# TE0722.net
KiCad netlist of a schematic drawn in Altium Designer
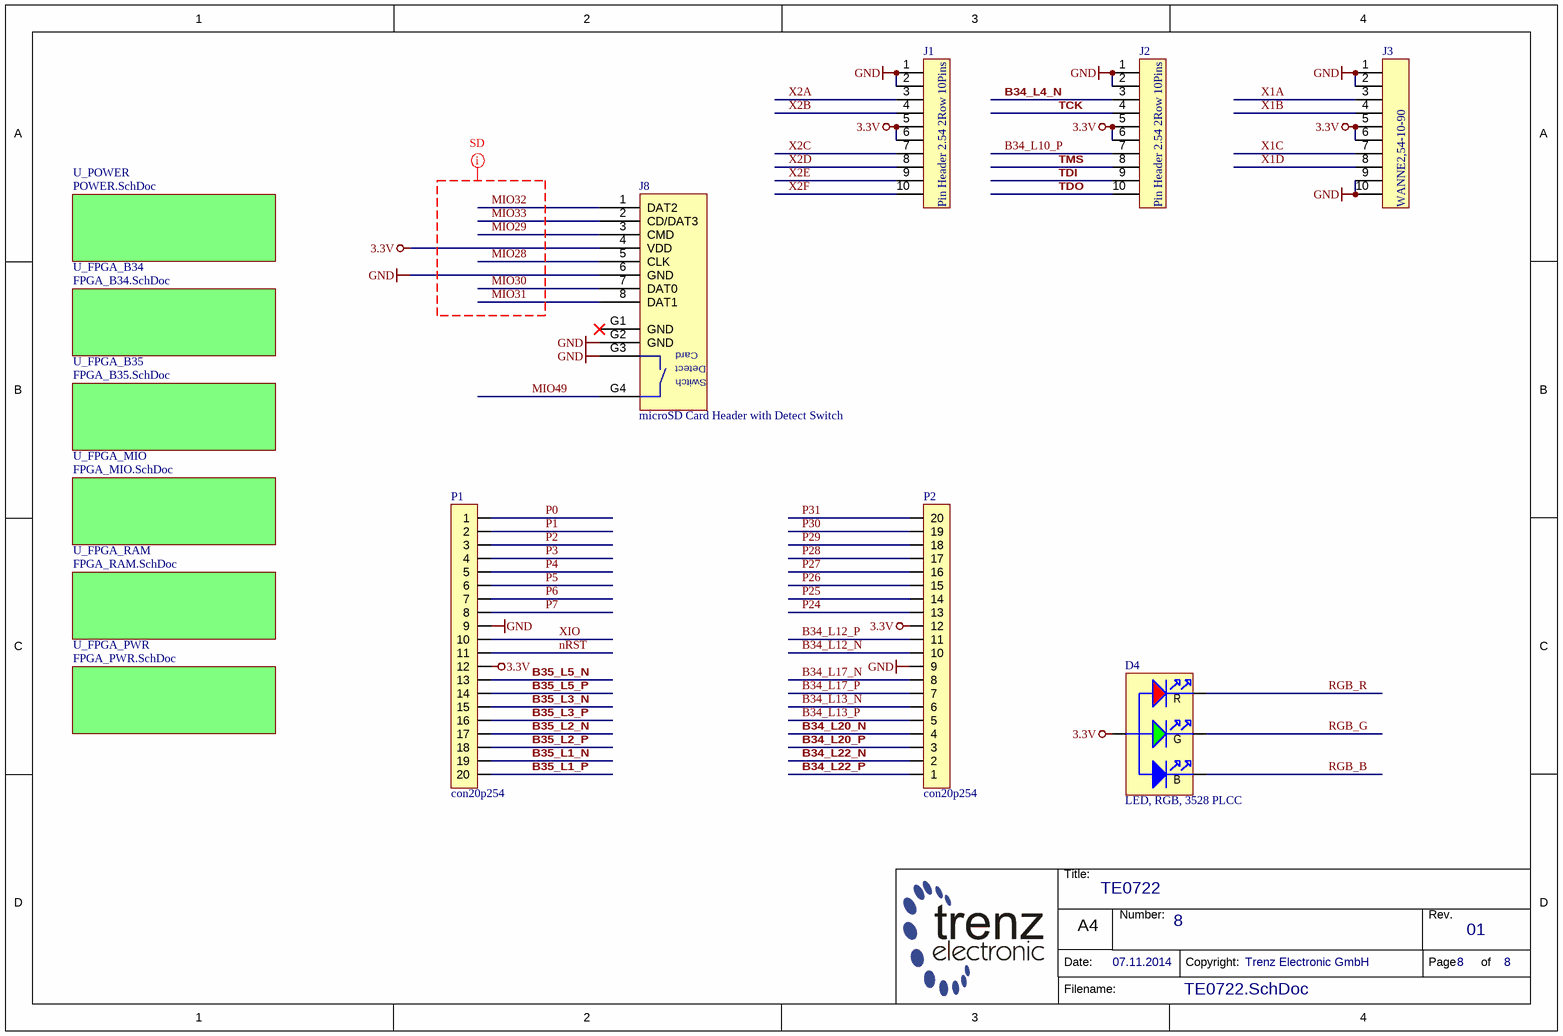
[diagram p0: TE0722.SchDoc]

(export (version "E")
  (design (tool "Eeschema 10.0.6"))
  (components
    (comp (ref "D4")
      (value "LED, RGB, 3528 PLCC")
      (footprint "PLCC150P360X280X190-4N")
      (libsource (lib "TE") (part "LED-RGB-3528"))
    )
    (comp (ref "J1")
      (value "Pin Header 2.54 2Row 10Pins")
      (footprint "STIFTLEISTE2_54 OG 2R-10")
      (description "Stiftleiste gerade 2-reihig, 10pol.")
      (libsource (lib "TE") (part "CON-10"))
    )
    (comp (ref "J2")
      (value "Pin Header 2.54 2Row 10Pins")
      (footprint "STIFTLEISTE2_54 OG 2R-10")
      (description "Stiftleiste gerade 2-reihig, 10pol.")
      (libsource (lib "TE") (part "CON-10"))
    )
    (comp (ref "J3")
      (value "WANNE2,54-10-90")
      (footprint "WANNE2,54-10-90")
      (description "Stiftleiste Wanne 10polig 90°")
      (libsource (lib "TE") (part "CON-10"))
    )
    (comp (ref "J8")
      (value "microSD Card Header with Detect Switch")
      (footprint "47309-2651")
      (libsource (lib "TE") (part "47309-2651"))
    )
    (comp (ref "P1")
      (value "con20p254")
      (footprint "con_20p254")
      (description "con_20pin_254_1row")
      (fields (field (name "Comment") "con_20pin"))
      (libsource (lib "trioflex-cadlib") (part "con_20pin"))
    )
    (comp (ref "P2")
      (value "con20p254")
      (footprint "con_20p254")
      (description "con_20pin_254_1row")
      (fields (field (name "Comment") "con_20pin"))
      (libsource (lib "") (part "con_20pin_1"))
    )
  )
  (nets
    (net (code "1") (name "/B34_L4_N") (class "Default")
      (node (ref "J2") (pin "3") (pinfunction "3_3") (pintype "passive"))
    )
    (net (code "2") (name "/B34_L10_P") (class "Default")
      (node (ref "J2") (pin "7") (pinfunction "7_7") (pintype "passive"))
    )
    (net (code "3") (name "/B34_L12_N") (class "Default")
      (node (ref "P2") (pin "10") (pinfunction "10_10") (pintype "passive"))
    )
    (net (code "4") (name "/B34_L12_P") (class "Default")
      (node (ref "P2") (pin "11") (pinfunction "11_11") (pintype "passive"))
    )
    (net (code "5") (name "/B34_L13_N") (class "Default")
      (node (ref "P2") (pin "6") (pinfunction "6_6") (pintype "passive"))
    )
    (net (code "6") (name "/B34_L13_P") (class "Default")
      (node (ref "P2") (pin "5") (pinfunction "5_5") (pintype "passive"))
    )
    (net (code "7") (name "/B34_L17_N") (class "Default")
      (node (ref "P2") (pin "8") (pinfunction "8_8") (pintype "passive"))
    )
    (net (code "8") (name "/B34_L17_P") (class "Default")
      (node (ref "P2") (pin "7") (pinfunction "7_7") (pintype "passive"))
    )
    (net (code "9") (name "/B34_L20_N") (class "Default")
      (node (ref "P2") (pin "4") (pinfunction "4_4") (pintype "passive"))
    )
    (net (code "10") (name "/B34_L20_P") (class "Default")
      (node (ref "P2") (pin "3") (pinfunction "3_3") (pintype "passive"))
    )
    (net (code "11") (name "/B34_L22_N") (class "Default")
      (node (ref "P2") (pin "2") (pinfunction "2_2") (pintype "passive"))
    )
    (net (code "12") (name "/B34_L22_P") (class "Default")
      (node (ref "P2") (pin "1") (pinfunction "1_1") (pintype "passive"))
    )
    (net (code "13") (name "/B35_L1_N") (class "Default")
      (node (ref "P1") (pin "19") (pinfunction "19_19") (pintype "passive"))
    )
    (net (code "14") (name "/B35_L1_P") (class "Default")
      (node (ref "P1") (pin "20") (pinfunction "20_20") (pintype "passive"))
    )
    (net (code "15") (name "/B35_L2_N") (class "Default")
      (node (ref "P1") (pin "17") (pinfunction "17_17") (pintype "passive"))
    )
    (net (code "16") (name "/B35_L2_P") (class "Default")
      (node (ref "P1") (pin "18") (pinfunction "18_18") (pintype "passive"))
    )
    (net (code "17") (name "/B35_L3_N") (class "Default")
      (node (ref "P1") (pin "15") (pinfunction "15_15") (pintype "passive"))
    )
    (net (code "18") (name "/B35_L3_P") (class "Default")
      (node (ref "P1") (pin "16") (pinfunction "16_16") (pintype "passive"))
    )
    (net (code "19") (name "/B35_L5_N") (class "Default")
      (node (ref "P1") (pin "13") (pinfunction "13_13") (pintype "passive"))
    )
    (net (code "20") (name "/B35_L5_P") (class "Default")
      (node (ref "P1") (pin "14") (pinfunction "14_14") (pintype "passive"))
    )
    (net (code "21") (name "/MIO28") (class "Default")
      (node (ref "J8") (pin "5") (pinfunction "CLK_5") (pintype "passive"))
    )
    (net (code "22") (name "/MIO29") (class "Default")
      (node (ref "J8") (pin "3") (pinfunction "CMD_3") (pintype "passive"))
    )
    (net (code "23") (name "/MIO30") (class "Default")
      (node (ref "J8") (pin "7") (pinfunction "DAT0_7") (pintype "passive"))
    )
    (net (code "24") (name "/MIO31") (class "Default")
      (node (ref "J8") (pin "8") (pinfunction "DAT1_8") (pintype "passive"))
    )
    (net (code "25") (name "/MIO32") (class "Default")
      (node (ref "J8") (pin "1") (pinfunction "DAT2_1") (pintype "passive"))
    )
    (net (code "26") (name "/MIO33") (class "Default")
      (node (ref "J8") (pin "2") (pinfunction "CD/DAT3_2") (pintype "passive"))
    )
    (net (code "27") (name "/MIO49") (class "Default")
      (node (ref "J8") (pin "G4") (pinfunction "DET_G4") (pintype "passive"))
    )
    (net (code "28") (name "/P0") (class "Default")
      (node (ref "P1") (pin "1") (pinfunction "1_1") (pintype "passive"))
    )
    (net (code "29") (name "/P1") (class "Default")
      (node (ref "P1") (pin "2") (pinfunction "2_2") (pintype "passive"))
    )
    (net (code "30") (name "/P2") (class "Default")
      (node (ref "P1") (pin "3") (pinfunction "3_3") (pintype "passive"))
    )
    (net (code "31") (name "/P3") (class "Default")
      (node (ref "P1") (pin "4") (pinfunction "4_4") (pintype "passive"))
    )
    (net (code "32") (name "/P4") (class "Default")
      (node (ref "P1") (pin "5") (pinfunction "5_5") (pintype "passive"))
    )
    (net (code "33") (name "/P5") (class "Default")
      (node (ref "P1") (pin "6") (pinfunction "6_6") (pintype "passive"))
    )
    (net (code "34") (name "/P6") (class "Default")
      (node (ref "P1") (pin "7") (pinfunction "7_7") (pintype "passive"))
    )
    (net (code "35") (name "/P7") (class "Default")
      (node (ref "P1") (pin "8") (pinfunction "8_8") (pintype "passive"))
    )
    (net (code "36") (name "/P24") (class "Default")
      (node (ref "P2") (pin "13") (pinfunction "13_13") (pintype "passive"))
    )
    (net (code "37") (name "/P25") (class "Default")
      (node (ref "P2") (pin "14") (pinfunction "14_14") (pintype "passive"))
    )
    (net (code "38") (name "/P26") (class "Default")
      (node (ref "P2") (pin "15") (pinfunction "15_15") (pintype "passive"))
    )
    (net (code "39") (name "/P27") (class "Default")
      (node (ref "P2") (pin "16") (pinfunction "16_16") (pintype "passive"))
    )
    (net (code "40") (name "/P28") (class "Default")
      (node (ref "P2") (pin "17") (pinfunction "17_17") (pintype "passive"))
    )
    (net (code "41") (name "/P29") (class "Default")
      (node (ref "P2") (pin "18") (pinfunction "18_18") (pintype "passive"))
    )
    (net (code "42") (name "/P30") (class "Default")
      (node (ref "P2") (pin "19") (pinfunction "19_19") (pintype "passive"))
    )
    (net (code "43") (name "/P31") (class "Default")
      (node (ref "P2") (pin "20") (pinfunction "20_20") (pintype "passive"))
    )
    (net (code "44") (name "/RGB_B") (class "Default")
      (node (ref "D4") (pin "4") (pinfunction "BLUE_4") (pintype "passive"))
    )
    (net (code "45") (name "/RGB_G") (class "Default")
      (node (ref "D4") (pin "2") (pinfunction "GREEN_2") (pintype "passive"))
    )
    (net (code "46") (name "/RGB_R") (class "Default")
      (node (ref "D4") (pin "1") (pinfunction "RED_1") (pintype "passive"))
    )
    (net (code "47") (name "/TCK") (class "Default")
      (node (ref "J2") (pin "4") (pinfunction "4_4") (pintype "passive"))
    )
    (net (code "48") (name "/TDI") (class "Default")
      (node (ref "J2") (pin "9") (pinfunction "9_9") (pintype "passive"))
    )
    (net (code "49") (name "/TDO") (class "Default")
      (node (ref "J2") (pin "10") (pinfunction "10_10") (pintype "passive"))
    )
    (net (code "50") (name "/TMS") (class "Default")
      (node (ref "J2") (pin "8") (pinfunction "8_8") (pintype "passive"))
    )
    (net (code "51") (name "/X1A") (class "Default")
      (node (ref "J3") (pin "3") (pinfunction "3_3") (pintype "passive"))
    )
    (net (code "52") (name "/X1B") (class "Default")
      (node (ref "J3") (pin "4") (pinfunction "4_4") (pintype "passive"))
    )
    (net (code "53") (name "/X1C") (class "Default")
      (node (ref "J3") (pin "7") (pinfunction "7_7") (pintype "passive"))
    )
    (net (code "54") (name "/X1D") (class "Default")
      (node (ref "J3") (pin "8") (pinfunction "8_8") (pintype "passive"))
    )
    (net (code "55") (name "/X2A") (class "Default")
      (node (ref "J1") (pin "3") (pinfunction "3_3") (pintype "passive"))
    )
    (net (code "56") (name "/X2B") (class "Default")
      (node (ref "J1") (pin "4") (pinfunction "4_4") (pintype "passive"))
    )
    (net (code "57") (name "/X2C") (class "Default")
      (node (ref "J1") (pin "7") (pinfunction "7_7") (pintype "passive"))
    )
    (net (code "58") (name "/X2D") (class "Default")
      (node (ref "J1") (pin "8") (pinfunction "8_8") (pintype "passive"))
    )
    (net (code "59") (name "/X2E") (class "Default")
      (node (ref "J1") (pin "9") (pinfunction "9_9") (pintype "passive"))
    )
    (net (code "60") (name "/X2F") (class "Default")
      (node (ref "J1") (pin "10") (pinfunction "10_10") (pintype "passive"))
    )
    (net (code "61") (name "/XIO") (class "Default")
      (node (ref "P1") (pin "10") (pinfunction "10_10") (pintype "passive"))
    )
    (net (code "62") (name "/nRST") (class "Default")
      (node (ref "P1") (pin "11") (pinfunction "11_11") (pintype "passive"))
    )
    (net (code "63") (name "3.3V") (class "Default")
      (node (ref "D4") (pin "3") (pinfunction "ANODE_3") (pintype "passive"))
      (node (ref "J1") (pin "5") (pinfunction "5_5") (pintype "passive"))
      (node (ref "J1") (pin "6") (pinfunction "6_6") (pintype "passive"))
      (node (ref "J2") (pin "5") (pinfunction "5_5") (pintype "passive"))
      (node (ref "J2") (pin "6") (pinfunction "6_6") (pintype "passive"))
      (node (ref "J3") (pin "5") (pinfunction "5_5") (pintype "passive"))
      (node (ref "J3") (pin "6") (pinfunction "6_6") (pintype "passive"))
      (node (ref "J8") (pin "4") (pinfunction "VDD_4") (pintype "passive"))
      (node (ref "P1") (pin "12") (pinfunction "12_12") (pintype "passive"))
      (node (ref "P2") (pin "12") (pinfunction "12_12") (pintype "passive"))
    )
    (net (code "64") (name "GND") (class "Default")
      (node (ref "J1") (pin "1") (pinfunction "1_1") (pintype "passive"))
      (node (ref "J1") (pin "2") (pinfunction "2_2") (pintype "passive"))
      (node (ref "J2") (pin "1") (pinfunction "1_1") (pintype "passive"))
      (node (ref "J2") (pin "2") (pinfunction "2_2") (pintype "passive"))
      (node (ref "J3") (pin "1") (pinfunction "1_1") (pintype "passive"))
      (node (ref "J3") (pin "10") (pinfunction "10_10") (pintype "passive"))
      (node (ref "J3") (pin "2") (pinfunction "2_2") (pintype "passive"))
      (node (ref "J3") (pin "9") (pinfunction "9_9") (pintype "passive"))
      (node (ref "J8") (pin "6") (pinfunction "GND_6") (pintype "passive"))
      (node (ref "J8") (pin "G2") (pinfunction "GND_G2") (pintype "passive"))
      (node (ref "J8") (pin "G3") (pinfunction "POL_G3") (pintype "passive"))
      (node (ref "P1") (pin "9") (pinfunction "9_9") (pintype "passive"))
      (node (ref "P2") (pin "9") (pinfunction "9_9") (pintype "passive"))
    )
    (net (code "65") (name "unconnected-(J8-GND-PadG1)") (class "Default")
      (node (ref "J8") (pin "G1") (pinfunction "GND_G1") (pintype "passive+no_connect"))
    )
  )
)
